# design.net
KiCad netlist of a schematic drawn in EasyEDA Pro
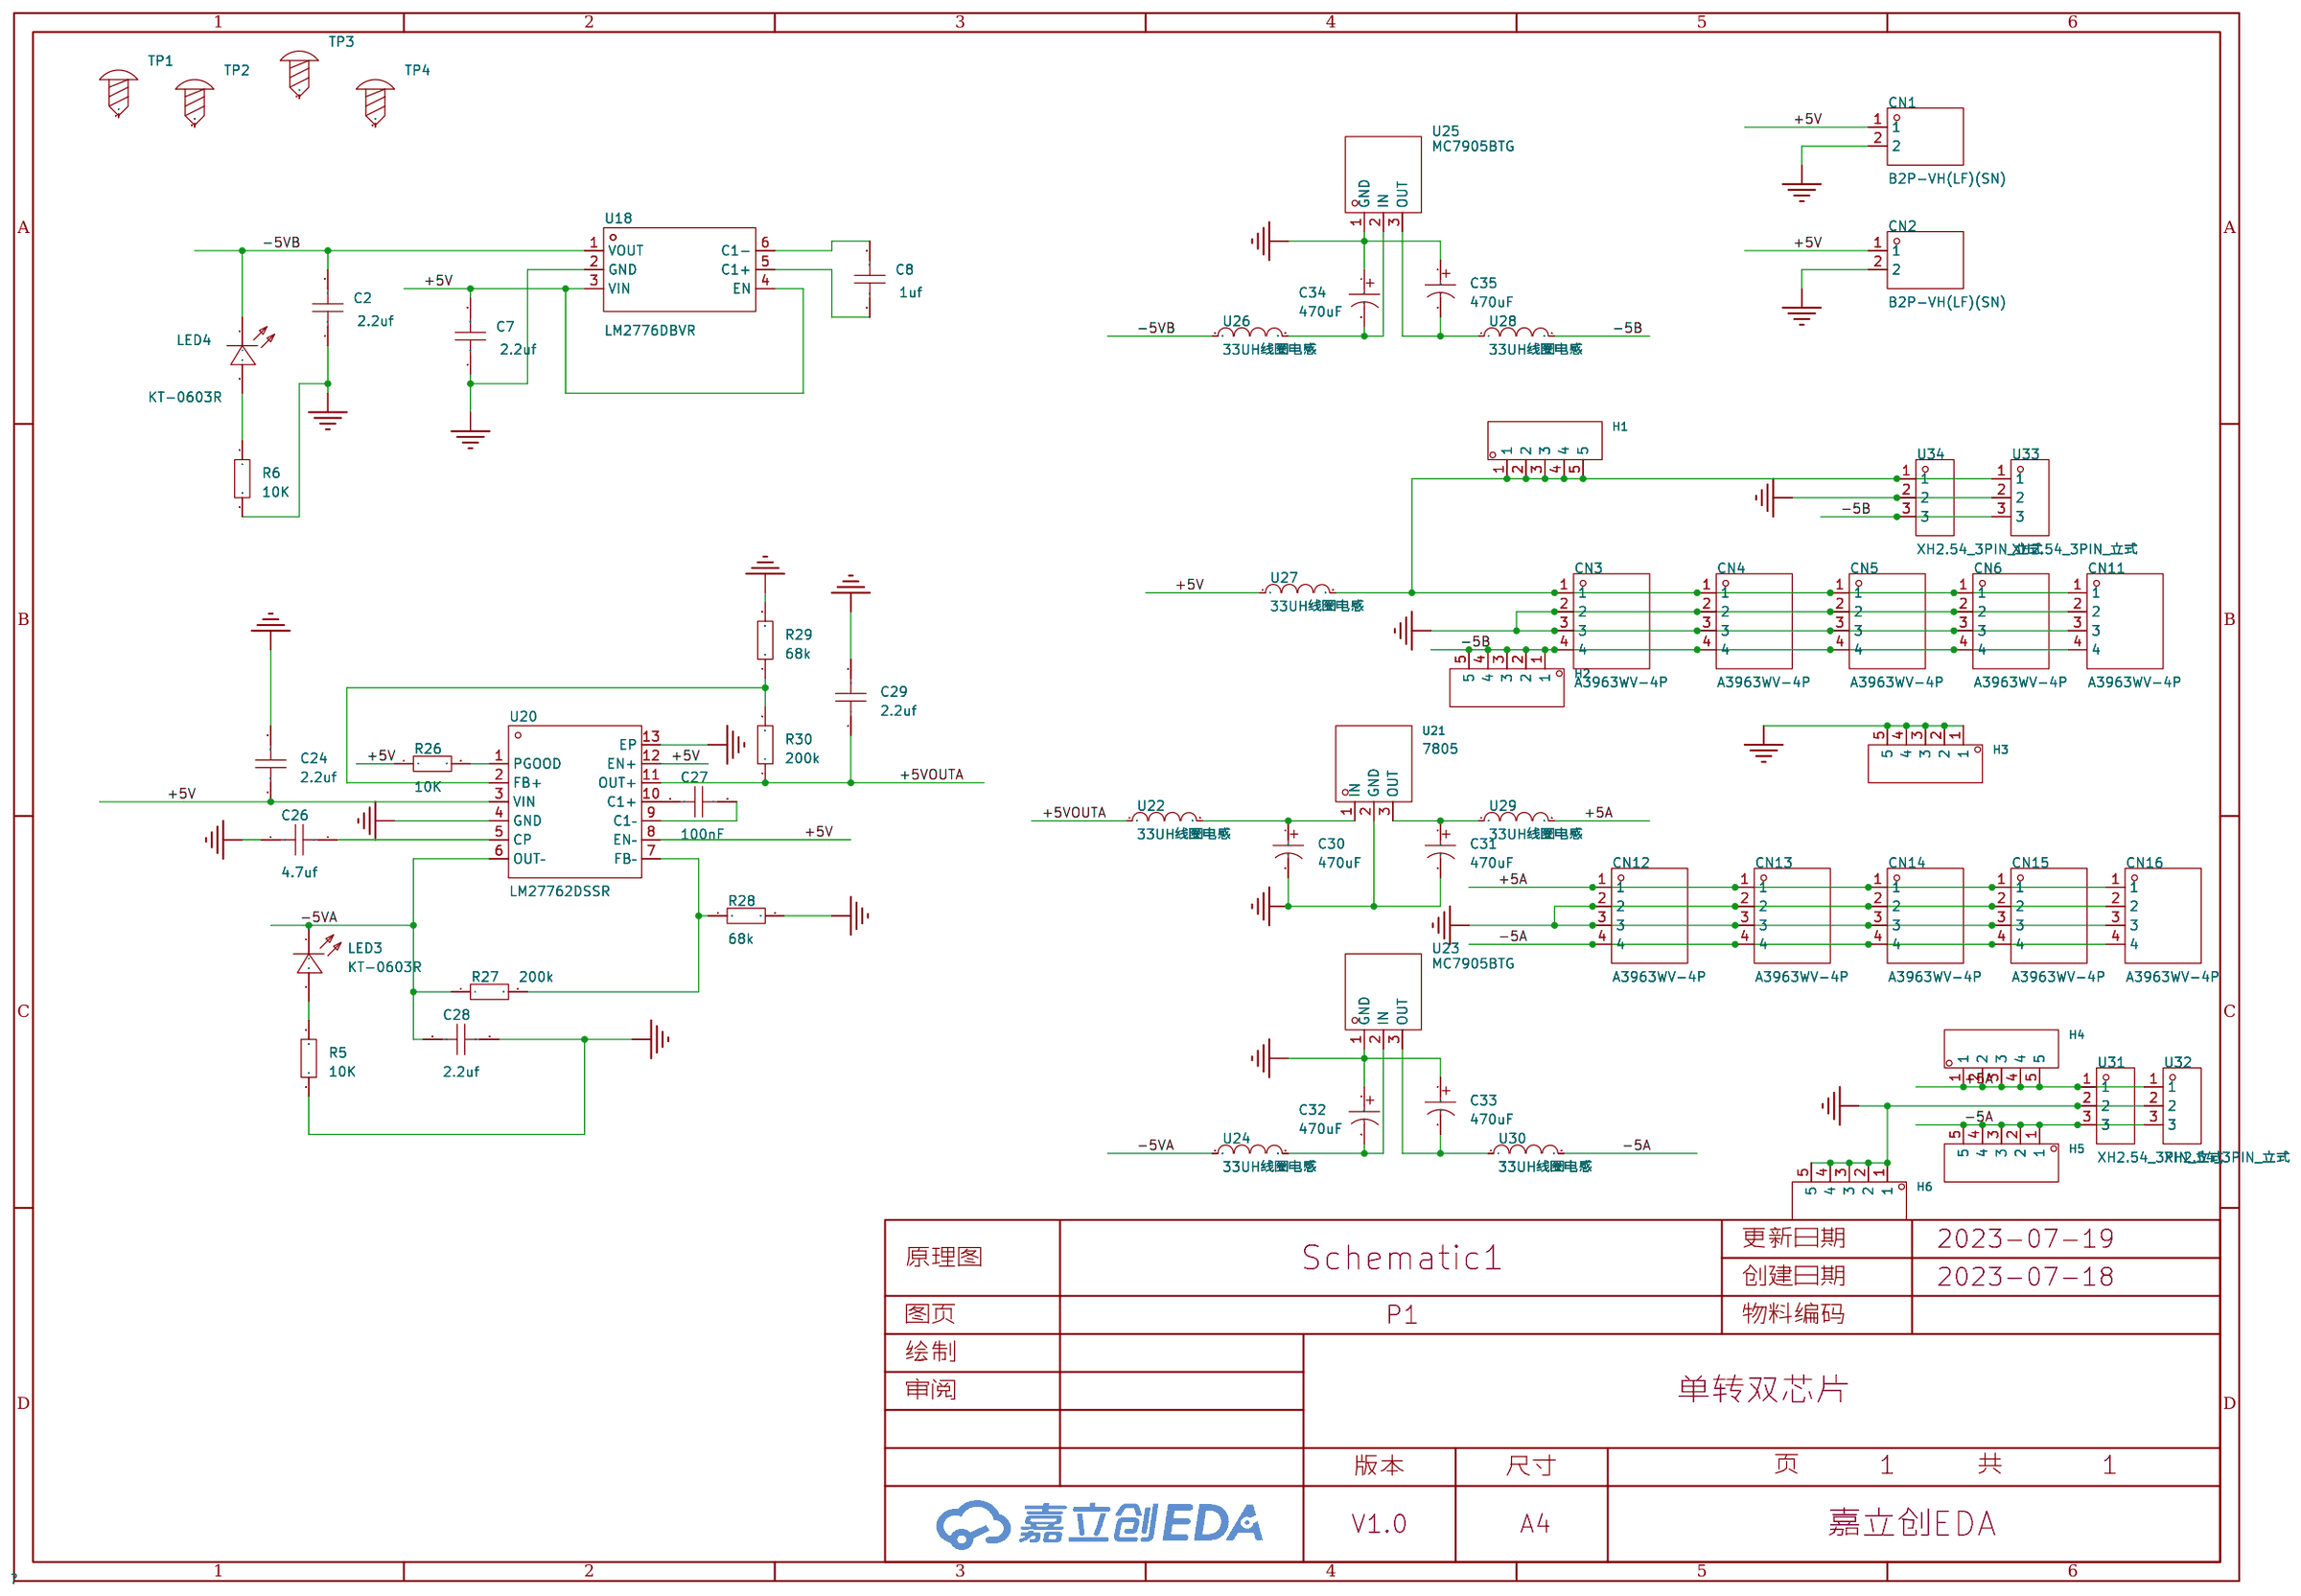
[diagram p0: schematic sheet]

(export (version "E")
  (design (tool "Eeschema 10.0.6"))
  (components
    (comp (ref "C2")
      (value "2.2uf")
      (footprint "easyedapro:C0603")
      (libsource (lib "easyedapro") (part "CapAcitance"))
    )
    (comp (ref "C7")
      (value "2.2uf")
      (footprint "easyedapro:C0603")
      (libsource (lib "easyedapro") (part "CapAcitance"))
    )
    (comp (ref "C8")
      (value "1uf")
      (footprint "easyedapro:C0603")
      (libsource (lib "easyedapro") (part "CapAcitance"))
    )
    (comp (ref "C24")
      (value "2.2uf")
      (footprint "easyedapro:C0603")
      (libsource (lib "easyedapro") (part "CapAcitance"))
    )
    (comp (ref "C26")
      (value "4.7uf")
      (footprint "easyedapro:C0603")
      (libsource (lib "easyedapro") (part "CapAcitance"))
    )
    (comp (ref "C27")
      (value "100nF")
      (footprint "easyedapro:C0603")
      (libsource (lib "easyedapro") (part "CapAcitance"))
    )
    (comp (ref "C28")
      (value "2.2uf")
      (footprint "easyedapro:C0603")
      (libsource (lib "easyedapro") (part "CapAcitance"))
    )
    (comp (ref "C29")
      (value "2.2uf")
      (footprint "easyedapro:C0603")
      (libsource (lib "easyedapro") (part "CapAcitance"))
    )
    (comp (ref "C30")
      (value "470uF")
      (footprint "easyedapro:CAP-TH_BD8.0-P3.50-D0.6-FD")
      (description "容值:470uF;精度:±20%;额定电压:25V;")
      (fields
        (field (name "Manufacturer Part") "KM477M025F12RR0VH2FP0")
        (field (name "Manufacturer") "CX(承兴)")
      )
      (libsource (lib "easyedapro") (part "470uF 25V 8*12"))
    )
    (comp (ref "C31")
      (value "470uF")
      (footprint "easyedapro:CAP-TH_BD8.0-P3.50-D0.6-FD")
      (description "容值:470uF;精度:±20%;额定电压:25V;")
      (fields
        (field (name "Manufacturer Part") "KM477M025F12RR0VH2FP0")
        (field (name "Manufacturer") "CX(承兴)")
      )
      (libsource (lib "easyedapro") (part "470uF 25V 8*12"))
    )
    (comp (ref "C32")
      (value "470uF")
      (footprint "easyedapro:CAP-TH_BD8.0-P3.50-D0.6-FD")
      (description "容值:470uF;精度:±20%;额定电压:25V;")
      (fields
        (field (name "Manufacturer Part") "KM477M025F12RR0VH2FP0")
        (field (name "Manufacturer") "CX(承兴)")
      )
      (libsource (lib "easyedapro") (part "470uF 25V 8*12"))
    )
    (comp (ref "C33")
      (value "470uF")
      (footprint "easyedapro:CAP-TH_BD8.0-P3.50-D0.6-FD")
      (description "容值:470uF;精度:±20%;额定电压:25V;")
      (fields
        (field (name "Manufacturer Part") "KM477M025F12RR0VH2FP0")
        (field (name "Manufacturer") "CX(承兴)")
      )
      (libsource (lib "easyedapro") (part "470uF 25V 8*12"))
    )
    (comp (ref "C34")
      (value "470uF")
      (footprint "easyedapro:CAP-TH_BD8.0-P3.50-D0.6-FD")
      (description "容值:470uF;精度:±20%;额定电压:25V;")
      (fields
        (field (name "Manufacturer Part") "KM477M025F12RR0VH2FP0")
        (field (name "Manufacturer") "CX(承兴)")
      )
      (libsource (lib "easyedapro") (part "470uF 25V 8*12"))
    )
    (comp (ref "C35")
      (value "470uF")
      (footprint "easyedapro:CAP-TH_BD8.0-P3.50-D0.6-FD")
      (description "容值:470uF;精度:±20%;额定电压:25V;")
      (fields
        (field (name "Manufacturer Part") "KM477M025F12RR0VH2FP0")
        (field (name "Manufacturer") "CX(承兴)")
      )
      (libsource (lib "easyedapro") (part "470uF 25V 8*12"))
    )
    (comp (ref "CN1")
      (value "B2P-VH(LF)(SN)")
      (footprint "easyedapro:CONN-TH_B2P-VH-LF-SN")
      (description "参考系列:VH;间距:3.96mm;插针结构:1x2P;排数:1;每排PIN数:2;行距:-;安装方式:-;触头材质:黄铜;")
      (fields (field (name "Manufacturer") "JST"))
      (libsource (lib "easyedapro") (part "B2P-VH(LF)(SN)"))
    )
    (comp (ref "CN2")
      (value "B2P-VH(LF)(SN)")
      (footprint "easyedapro:CONN-TH_B2P-VH-LF-SN")
      (description "参考系列:VH;间距:3.96mm;插针结构:1x2P;排数:1;每排PIN数:2;行距:-;安装方式:-;触头材质:黄铜;")
      (fields (field (name "Manufacturer") "JST"))
      (libsource (lib "easyedapro") (part "B2P-VH(LF)(SN)"))
    )
    (comp (ref "CN3")
      (value "A3963WV-4P")
      (footprint "easyedapro:CONN-TH_A3963WV-4P")
      (description "参考系列:VH;间距:3.96mm;插针结构:1x4P;排数:1;每排PIN数:4;行距:-;安装方式:-;触头材质:黄铜;")
      (fields (field (name "Manufacturer") "CJT(长江连接器)"))
      (libsource (lib "easyedapro") (part "A3963WV-4P"))
    )
    (comp (ref "CN4")
      (value "A3963WV-4P")
      (footprint "easyedapro:CONN-TH_A3963WV-4P")
      (description "参考系列:VH;间距:3.96mm;插针结构:1x4P;排数:1;每排PIN数:4;行距:-;安装方式:-;触头材质:黄铜;")
      (fields (field (name "Manufacturer") "CJT(长江连接器)"))
      (libsource (lib "easyedapro") (part "A3963WV-4P"))
    )
    (comp (ref "CN5")
      (value "A3963WV-4P")
      (footprint "easyedapro:CONN-TH_A3963WV-4P")
      (description "参考系列:VH;间距:3.96mm;插针结构:1x4P;排数:1;每排PIN数:4;行距:-;安装方式:-;触头材质:黄铜;")
      (fields (field (name "Manufacturer") "CJT(长江连接器)"))
      (libsource (lib "easyedapro") (part "A3963WV-4P"))
    )
    (comp (ref "CN6")
      (value "A3963WV-4P")
      (footprint "easyedapro:CONN-TH_A3963WV-4P")
      (description "参考系列:VH;间距:3.96mm;插针结构:1x4P;排数:1;每排PIN数:4;行距:-;安装方式:-;触头材质:黄铜;")
      (fields (field (name "Manufacturer") "CJT(长江连接器)"))
      (libsource (lib "easyedapro") (part "A3963WV-4P"))
    )
    (comp (ref "CN11")
      (value "A3963WV-4P")
      (footprint "easyedapro:CONN-TH_A3963WV-4P")
      (description "参考系列:VH;间距:3.96mm;插针结构:1x4P;排数:1;每排PIN数:4;行距:-;安装方式:-;触头材质:黄铜;")
      (fields (field (name "Manufacturer") "CJT(长江连接器)"))
      (libsource (lib "easyedapro") (part "A3963WV-4P"))
    )
    (comp (ref "CN12")
      (value "A3963WV-4P")
      (footprint "easyedapro:CONN-TH_A3963WV-4P")
      (description "参考系列:VH;间距:3.96mm;插针结构:1x4P;排数:1;每排PIN数:4;行距:-;安装方式:-;触头材质:黄铜;")
      (fields (field (name "Manufacturer") "CJT(长江连接器)"))
      (libsource (lib "easyedapro") (part "A3963WV-4P"))
    )
    (comp (ref "CN13")
      (value "A3963WV-4P")
      (footprint "easyedapro:CONN-TH_A3963WV-4P")
      (description "参考系列:VH;间距:3.96mm;插针结构:1x4P;排数:1;每排PIN数:4;行距:-;安装方式:-;触头材质:黄铜;")
      (fields (field (name "Manufacturer") "CJT(长江连接器)"))
      (libsource (lib "easyedapro") (part "A3963WV-4P"))
    )
    (comp (ref "CN14")
      (value "A3963WV-4P")
      (footprint "easyedapro:CONN-TH_A3963WV-4P")
      (description "参考系列:VH;间距:3.96mm;插针结构:1x4P;排数:1;每排PIN数:4;行距:-;安装方式:-;触头材质:黄铜;")
      (fields (field (name "Manufacturer") "CJT(长江连接器)"))
      (libsource (lib "easyedapro") (part "A3963WV-4P"))
    )
    (comp (ref "CN15")
      (value "A3963WV-4P")
      (footprint "easyedapro:CONN-TH_A3963WV-4P")
      (description "参考系列:VH;间距:3.96mm;插针结构:1x4P;排数:1;每排PIN数:4;行距:-;安装方式:-;触头材质:黄铜;")
      (fields (field (name "Manufacturer") "CJT(长江连接器)"))
      (libsource (lib "easyedapro") (part "A3963WV-4P"))
    )
    (comp (ref "CN16")
      (value "A3963WV-4P")
      (footprint "easyedapro:CONN-TH_A3963WV-4P")
      (description "参考系列:VH;间距:3.96mm;插针结构:1x4P;排数:1;每排PIN数:4;行距:-;安装方式:-;触头材质:黄铜;")
      (fields (field (name "Manufacturer") "CJT(长江连接器)"))
      (libsource (lib "easyedapro") (part "A3963WV-4P"))
    )
    (comp (ref "H1")
      (value "~")
      (footprint "easyedapro:HDR-TH_5P-P2.54-V-M")
      (libsource (lib "easyedapro") (part "MTP125-1105S1"))
    )
    (comp (ref "H2")
      (value "~")
      (footprint "easyedapro:HDR-TH_5P-P2.54-V-M")
      (libsource (lib "easyedapro") (part "MTP125-1105S1"))
    )
    (comp (ref "H3")
      (value "~")
      (footprint "easyedapro:HDR-TH_5P-P2.54-V-M")
      (libsource (lib "easyedapro") (part "MTP125-1105S1"))
    )
    (comp (ref "H4")
      (value "~")
      (footprint "easyedapro:HDR-TH_5P-P2.54-V-M")
      (libsource (lib "easyedapro") (part "MTP125-1105S1"))
    )
    (comp (ref "H5")
      (value "~")
      (footprint "easyedapro:HDR-TH_5P-P2.54-V-M")
      (libsource (lib "easyedapro") (part "MTP125-1105S1"))
    )
    (comp (ref "H6")
      (value "~")
      (footprint "easyedapro:HDR-TH_5P-P2.54-V-M")
      (libsource (lib "easyedapro") (part "MTP125-1105S1"))
    )
    (comp (ref "LED3")
      (value "KT-0603R")
      (footprint "easyedapro:LED0603-RD")
      (description "发光颜色:红灯;二极管配置:-;透镜颜色:-;主波长:-;色温:-;功率:-;发光角度:-;安装方式:-;工作温度:-40℃~+85℃;")
      (fields (field (name "Manufacturer") "KENTO"))
      (libsource (lib "easyedapro") (part "KT-0603R"))
    )
    (comp (ref "LED4")
      (value "KT-0603R")
      (footprint "easyedapro:LED0603-RD")
      (description "发光颜色:红灯;二极管配置:-;透镜颜色:-;主波长:-;色温:-;功率:-;发光角度:-;安装方式:-;工作温度:-40℃~+85℃;")
      (fields (field (name "Manufacturer") "KENTO"))
      (libsource (lib "easyedapro") (part "KT-0603R"))
    )
    (comp (ref "R5") (value "10K") (footprint "easyedapro:R0603") (libsource (lib "easyedapro") (part "电阻")))
    (comp (ref "R6") (value "10K") (footprint "easyedapro:R0603") (libsource (lib "easyedapro") (part "电阻")))
    (comp (ref "R26") (value "10K") (footprint "easyedapro:R0603") (libsource (lib "easyedapro") (part "电阻")))
    (comp (ref "R27")
      (value "200k")
      (footprint "easyedapro:R0603")
      (libsource (lib "easyedapro") (part "电阻"))
    )
    (comp (ref "R28") (value "68k") (footprint "easyedapro:R0603") (libsource (lib "easyedapro") (part "电阻")))
    (comp (ref "R29") (value "68k") (footprint "easyedapro:R0603") (libsource (lib "easyedapro") (part "电阻")))
    (comp (ref "R30")
      (value "200k")
      (footprint "easyedapro:R0603")
      (libsource (lib "easyedapro") (part "电阻"))
    )
    (comp (ref "TP1") (value "~") (footprint "easyedapro:M3螺丝") (libsource (lib "easyedapro") (part "螺丝孔")))
    (comp (ref "TP2") (value "~") (footprint "easyedapro:M3螺丝") (libsource (lib "easyedapro") (part "螺丝孔")))
    (comp (ref "TP3") (value "~") (footprint "easyedapro:M3螺丝") (libsource (lib "easyedapro") (part "螺丝孔")))
    (comp (ref "TP4") (value "~") (footprint "easyedapro:M3螺丝") (libsource (lib "easyedapro") (part "螺丝孔")))
    (comp (ref "U18")
      (value "LM2776DBVR")
      (footprint "easyedapro:SOT-23-6_L2.9-W1.6-P0.95-LS2.8-BR")
      (description "可输出电流:200mA;开关工作频率:2MHz;输出类型:Fixed;输出电压的路数:1;功能类型:Ratiometric;输出配置:Negative;")
      (fields (field (name "Manufacturer") "TI(德州仪器)"))
      (libsource (lib "easyedapro") (part "LM2776DBVR"))
    )
    (comp (ref "U20")
      (value "LM27762DSSR")
      (footprint "easyedapro:WSON-12_L3.0-W2.0-P0.50-BL-EP")
      (description "功能类型:电荷泵;同步整流:否;输出通道数:2;拓扑结构:-;输入电压:2.7V~5.5V;输出电压:-5V~-1.5V；1.5V~5V;输出电流(最大值):250mA;开关频率:2.3MHz;")
      (fields (field (name "Manufacturer") "TI(德州仪器)"))
      (libsource (lib "easyedapro") (part "LM27762DSSR"))
    )
    (comp (ref "U21")
      (value "7805")
      (footprint "easyedapro:TO-220-3_L10.2-W4.5-P2.54-L-1")
      (description "输出类型:固定;输出极性:正;最大输入电压:35V;输出电压:5V;输出电流:1.5A;电源纹波抑制比(PSRR):62dB@(120Hz);")
      (fields (field (name "Manufacturer") "SY(顺烨）"))
      (libsource (lib "easyedapro") (part "7805_C4944936"))
    )
    (comp (ref "U22")
      (value "33UH线圈电感")
      (footprint "easyedapro:IND-TH_L5.4-W5.0")
      (libsource (lib "easyedapro") (part "33UH线圈电感"))
    )
    (comp (ref "U23")
      (value "MC7905BTG")
      (footprint "easyedapro:TO-220-3_L10.0-W4.5-P2.54-T")
      (description "输出类型:固定;输出极性:负;最大输入电压:35V;输出电压:5V;输出电流:1A;电源纹波抑制比(PSRR):70dB@(120Hz);")
      (fields (field (name "Manufacturer") "onsemi(安森美)"))
      (libsource (lib "easyedapro") (part "MC7905BTG"))
    )
    (comp (ref "U24")
      (value "33UH线圈电感")
      (footprint "easyedapro:IND-TH_L5.4-W5.0")
      (libsource (lib "easyedapro") (part "33UH线圈电感"))
    )
    (comp (ref "U25")
      (value "MC7905BTG")
      (footprint "easyedapro:TO-220-3_L10.0-W4.5-P2.54-T")
      (description "输出类型:固定;输出极性:负;最大输入电压:35V;输出电压:5V;输出电流:1A;电源纹波抑制比(PSRR):70dB@(120Hz);")
      (fields (field (name "Manufacturer") "onsemi(安森美)"))
      (libsource (lib "easyedapro") (part "MC7905BTG"))
    )
    (comp (ref "U26")
      (value "33UH线圈电感")
      (footprint "easyedapro:IND-TH_L5.4-W5.0")
      (libsource (lib "easyedapro") (part "33UH线圈电感"))
    )
    (comp (ref "U27")
      (value "33UH线圈电感")
      (footprint "easyedapro:IND-TH_L5.4-W5.0")
      (libsource (lib "easyedapro") (part "33UH线圈电感"))
    )
    (comp (ref "U28")
      (value "33UH线圈电感")
      (footprint "easyedapro:IND-TH_L5.4-W5.0")
      (libsource (lib "easyedapro") (part "33UH线圈电感"))
    )
    (comp (ref "U29")
      (value "33UH线圈电感")
      (footprint "easyedapro:IND-TH_L5.4-W5.0")
      (libsource (lib "easyedapro") (part "33UH线圈电感"))
    )
    (comp (ref "U30")
      (value "33UH线圈电感")
      (footprint "easyedapro:IND-TH_L5.4-W5.0")
      (libsource (lib "easyedapro") (part "33UH线圈电感"))
    )
    (comp (ref "U31")
      (value "XH2.54_3PIN_立式")
      (footprint "easyedapro:CONN-TH_XH2.54_3PIN")
      (libsource (lib "easyedapro") (part "XH2.54_3PIN"))
    )
    (comp (ref "U32")
      (value "XH2.54_3PIN_立式")
      (footprint "easyedapro:CONN-TH_XH2.54_3PIN")
      (libsource (lib "easyedapro") (part "XH2.54_3PIN"))
    )
    (comp (ref "U33")
      (value "XH2.54_3PIN_立式")
      (footprint "easyedapro:CONN-TH_XH2.54_3PIN")
      (libsource (lib "easyedapro") (part "XH2.54_3PIN"))
    )
    (comp (ref "U34")
      (value "XH2.54_3PIN_立式")
      (footprint "easyedapro:CONN-TH_XH2.54_3PIN")
      (libsource (lib "easyedapro") (part "XH2.54_3PIN"))
    )
  )
  (nets
    (net (code "1") (name "/+5A") (class "Default")
      (node (ref "CN12") (pin "1") (pinfunction "1_1") (pintype "input"))
      (node (ref "CN13") (pin "1") (pinfunction "1_1") (pintype "input"))
      (node (ref "CN14") (pin "1") (pinfunction "1_1") (pintype "input"))
      (node (ref "CN15") (pin "1") (pinfunction "1_1") (pintype "input"))
      (node (ref "CN16") (pin "1") (pinfunction "1_1") (pintype "input"))
      (node (ref "H4") (pin "1") (pinfunction "1_1") (pintype "input"))
      (node (ref "H4") (pin "2") (pinfunction "2_2") (pintype "input"))
      (node (ref "H4") (pin "3") (pinfunction "3_3") (pintype "input"))
      (node (ref "H4") (pin "4") (pinfunction "4_4") (pintype "input"))
      (node (ref "H4") (pin "5") (pinfunction "5_5") (pintype "input"))
      (node (ref "U29") (pin "2") (pinfunction "2_2") (pintype "input"))
      (node (ref "U31") (pin "1") (pinfunction "1_1") (pintype "input"))
      (node (ref "U32") (pin "1") (pinfunction "1_1") (pintype "input"))
    )
    (net (code "2") (name "/+5V") (class "Default")
      (node (ref "C24") (pin "1") (pinfunction "1_1") (pintype "input"))
      (node (ref "C7") (pin "2") (pinfunction "2_2") (pintype "input"))
      (node (ref "CN1") (pin "1") (pinfunction "1_1") (pintype "input"))
      (node (ref "CN2") (pin "1") (pinfunction "1_1") (pintype "input"))
      (node (ref "R26") (pin "1") (pinfunction "1_1") (pintype "input"))
      (node (ref "U18") (pin "3") (pinfunction "VIN_3") (pintype "input"))
      (node (ref "U18") (pin "4") (pinfunction "EN_4") (pintype "input"))
      (node (ref "U20") (pin "12") (pinfunction "EN+_12") (pintype "input"))
      (node (ref "U20") (pin "3") (pinfunction "VIN_3") (pintype "input"))
      (node (ref "U20") (pin "8") (pinfunction "EN–_8") (pintype "input"))
      (node (ref "U27") (pin "1") (pinfunction "1_1") (pintype "input"))
    )
    (net (code "3") (name "/+5VOUTA") (class "Default")
      (node (ref "C29") (pin "1") (pinfunction "1_1") (pintype "input"))
      (node (ref "R30") (pin "1") (pinfunction "1_1") (pintype "input"))
      (node (ref "U20") (pin "11") (pinfunction "OUT+_11") (pintype "input"))
      (node (ref "U22") (pin "1") (pinfunction "1_1") (pintype "input"))
    )
    (net (code "4") (name "/-5A") (class "Default")
      (node (ref "CN12") (pin "4") (pinfunction "4_4") (pintype "input"))
      (node (ref "CN13") (pin "4") (pinfunction "4_4") (pintype "input"))
      (node (ref "CN14") (pin "4") (pinfunction "4_4") (pintype "input"))
      (node (ref "CN15") (pin "4") (pinfunction "4_4") (pintype "input"))
      (node (ref "CN16") (pin "4") (pinfunction "4_4") (pintype "input"))
      (node (ref "H5") (pin "1") (pinfunction "1_1") (pintype "input"))
      (node (ref "H5") (pin "2") (pinfunction "2_2") (pintype "input"))
      (node (ref "H5") (pin "3") (pinfunction "3_3") (pintype "input"))
      (node (ref "H5") (pin "4") (pinfunction "4_4") (pintype "input"))
      (node (ref "H5") (pin "5") (pinfunction "5_5") (pintype "input"))
      (node (ref "U30") (pin "2") (pinfunction "2_2") (pintype "input"))
      (node (ref "U31") (pin "3") (pinfunction "3_3") (pintype "input"))
      (node (ref "U32") (pin "3") (pinfunction "3_3") (pintype "input"))
    )
    (net (code "5") (name "/-5B") (class "Default")
      (node (ref "CN11") (pin "4") (pinfunction "4_4") (pintype "input"))
      (node (ref "CN3") (pin "4") (pinfunction "4_4") (pintype "input"))
      (node (ref "CN4") (pin "4") (pinfunction "4_4") (pintype "input"))
      (node (ref "CN5") (pin "4") (pinfunction "4_4") (pintype "input"))
      (node (ref "CN6") (pin "4") (pinfunction "4_4") (pintype "input"))
      (node (ref "H2") (pin "1") (pinfunction "1_1") (pintype "input"))
      (node (ref "H2") (pin "2") (pinfunction "2_2") (pintype "input"))
      (node (ref "H2") (pin "3") (pinfunction "3_3") (pintype "input"))
      (node (ref "H2") (pin "4") (pinfunction "4_4") (pintype "input"))
      (node (ref "H2") (pin "5") (pinfunction "5_5") (pintype "input"))
      (node (ref "U28") (pin "2") (pinfunction "2_2") (pintype "input"))
      (node (ref "U33") (pin "3") (pinfunction "3_3") (pintype "input"))
      (node (ref "U34") (pin "3") (pinfunction "3_3") (pintype "input"))
    )
    (net (code "6") (name "/-5VA") (class "Default")
      (node (ref "C28") (pin "2") (pinfunction "2_2") (pintype "input"))
      (node (ref "LED3") (pin "1") (pinfunction "K_1") (pintype "input"))
      (node (ref "R27") (pin "1") (pinfunction "1_1") (pintype "input"))
      (node (ref "U20") (pin "6") (pinfunction "OUT–_6") (pintype "input"))
      (node (ref "U24") (pin "1") (pinfunction "1_1") (pintype "input"))
    )
    (net (code "7") (name "/-5VB") (class "Default")
      (node (ref "C2") (pin "2") (pinfunction "2_2") (pintype "input"))
      (node (ref "LED4") (pin "1") (pinfunction "K_1") (pintype "input"))
      (node (ref "U18") (pin "1") (pinfunction "VOUT_1") (pintype "input"))
      (node (ref "U26") (pin "1") (pinfunction "1_1") (pintype "input"))
    )
    (net (code "8") (name "GND") (class "Default")
      (node (ref "C2") (pin "1") (pinfunction "1_1") (pintype "input"))
      (node (ref "C24") (pin "2") (pinfunction "2_2") (pintype "input"))
      (node (ref "C26") (pin "2") (pinfunction "2_2") (pintype "input"))
      (node (ref "C28") (pin "1") (pinfunction "1_1") (pintype "input"))
      (node (ref "C29") (pin "2") (pinfunction "2_2") (pintype "input"))
      (node (ref "C30") (pin "2") (pinfunction "2_2") (pintype "input"))
      (node (ref "C31") (pin "2") (pinfunction "2_2") (pintype "input"))
      (node (ref "C32") (pin "1") (pinfunction "1_1") (pintype "input"))
      (node (ref "C33") (pin "1") (pinfunction "1_1") (pintype "input"))
      (node (ref "C34") (pin "1") (pinfunction "1_1") (pintype "input"))
      (node (ref "C35") (pin "1") (pinfunction "1_1") (pintype "input"))
      (node (ref "C7") (pin "1") (pinfunction "1_1") (pintype "input"))
      (node (ref "CN1") (pin "2") (pinfunction "2_2") (pintype "input"))
      (node (ref "CN11") (pin "2") (pinfunction "2_2") (pintype "input"))
      (node (ref "CN11") (pin "3") (pinfunction "3_3") (pintype "input"))
      (node (ref "CN12") (pin "2") (pinfunction "2_2") (pintype "input"))
      (node (ref "CN12") (pin "3") (pinfunction "3_3") (pintype "input"))
      (node (ref "CN13") (pin "2") (pinfunction "2_2") (pintype "input"))
      (node (ref "CN13") (pin "3") (pinfunction "3_3") (pintype "input"))
      (node (ref "CN14") (pin "2") (pinfunction "2_2") (pintype "input"))
      (node (ref "CN14") (pin "3") (pinfunction "3_3") (pintype "input"))
      (node (ref "CN15") (pin "2") (pinfunction "2_2") (pintype "input"))
      (node (ref "CN15") (pin "3") (pinfunction "3_3") (pintype "input"))
      (node (ref "CN16") (pin "2") (pinfunction "2_2") (pintype "input"))
      (node (ref "CN16") (pin "3") (pinfunction "3_3") (pintype "input"))
      (node (ref "CN2") (pin "2") (pinfunction "2_2") (pintype "input"))
      (node (ref "CN3") (pin "2") (pinfunction "2_2") (pintype "input"))
      (node (ref "CN3") (pin "3") (pinfunction "3_3") (pintype "input"))
      (node (ref "CN4") (pin "2") (pinfunction "2_2") (pintype "input"))
      (node (ref "CN4") (pin "3") (pinfunction "3_3") (pintype "input"))
      (node (ref "CN5") (pin "2") (pinfunction "2_2") (pintype "input"))
      (node (ref "CN5") (pin "3") (pinfunction "3_3") (pintype "input"))
      (node (ref "CN6") (pin "2") (pinfunction "2_2") (pintype "input"))
      (node (ref "CN6") (pin "3") (pinfunction "3_3") (pintype "input"))
      (node (ref "H3") (pin "1") (pinfunction "1_1") (pintype "input"))
      (node (ref "H3") (pin "2") (pinfunction "2_2") (pintype "input"))
      (node (ref "H3") (pin "3") (pinfunction "3_3") (pintype "input"))
      (node (ref "H3") (pin "4") (pinfunction "4_4") (pintype "input"))
      (node (ref "H3") (pin "5") (pinfunction "5_5") (pintype "input"))
      (node (ref "H6") (pin "1") (pinfunction "1_1") (pintype "input"))
      (node (ref "H6") (pin "2") (pinfunction "2_2") (pintype "input"))
      (node (ref "H6") (pin "3") (pinfunction "3_3") (pintype "input"))
      (node (ref "H6") (pin "4") (pinfunction "4_4") (pintype "input"))
      (node (ref "H6") (pin "5") (pinfunction "5_5") (pintype "input"))
      (node (ref "R28") (pin "2") (pinfunction "2_2") (pintype "input"))
      (node (ref "R29") (pin "2") (pinfunction "2_2") (pintype "input"))
      (node (ref "R5") (pin "2") (pinfunction "2_2") (pintype "input"))
      (node (ref "R6") (pin "2") (pinfunction "2_2") (pintype "input"))
      (node (ref "U18") (pin "2") (pinfunction "GND_2") (pintype "input"))
      (node (ref "U20") (pin "13") (pinfunction "EP_13") (pintype "input"))
      (node (ref "U20") (pin "4") (pinfunction "GND_4") (pintype "input"))
      (node (ref "U21") (pin "2") (pinfunction "GND_2") (pintype "input"))
      (node (ref "U23") (pin "1") (pinfunction "GND_1") (pintype "input"))
      (node (ref "U25") (pin "1") (pinfunction "GND_1") (pintype "input"))
      (node (ref "U31") (pin "2") (pinfunction "2_2") (pintype "input"))
      (node (ref "U32") (pin "2") (pinfunction "2_2") (pintype "input"))
      (node (ref "U33") (pin "2") (pinfunction "2_2") (pintype "input"))
      (node (ref "U34") (pin "2") (pinfunction "2_2") (pintype "input"))
    )
    (net (code "9") (name "Net-(CN11-Pad1)") (class "Default")
      (node (ref "CN11") (pin "1") (pinfunction "1_1") (pintype "input"))
      (node (ref "CN3") (pin "1") (pinfunction "1_1") (pintype "input"))
      (node (ref "CN4") (pin "1") (pinfunction "1_1") (pintype "input"))
      (node (ref "CN5") (pin "1") (pinfunction "1_1") (pintype "input"))
      (node (ref "CN6") (pin "1") (pinfunction "1_1") (pintype "input"))
      (node (ref "H1") (pin "1") (pinfunction "1_1") (pintype "input"))
      (node (ref "H1") (pin "2") (pinfunction "2_2") (pintype "input"))
      (node (ref "H1") (pin "3") (pinfunction "3_3") (pintype "input"))
      (node (ref "H1") (pin "4") (pinfunction "4_4") (pintype "input"))
      (node (ref "H1") (pin "5") (pinfunction "5_5") (pintype "input"))
      (node (ref "U27") (pin "2") (pinfunction "2_2") (pintype "input"))
      (node (ref "U33") (pin "1") (pinfunction "1_1") (pintype "input"))
      (node (ref "U34") (pin "1") (pinfunction "1_1") (pintype "input"))
    )
    (net (code "10") (name "Net-(LED3-A)") (class "Default")
      (node (ref "LED3") (pin "2") (pinfunction "A_2") (pintype "input"))
      (node (ref "R5") (pin "1") (pinfunction "1_1") (pintype "input"))
    )
    (net (code "11") (name "Net-(LED4-A)") (class "Default")
      (node (ref "LED4") (pin "2") (pinfunction "A_2") (pintype "input"))
      (node (ref "R6") (pin "1") (pinfunction "1_1") (pintype "input"))
    )
    (net (code "12") (name "Net-(U18-C1+)") (class "Default")
      (node (ref "C8") (pin "1") (pinfunction "1_1") (pintype "input"))
      (node (ref "U18") (pin "5") (pinfunction "C1+_5") (pintype "input"))
    )
    (net (code "13") (name "Net-(U18-C1-)") (class "Default")
      (node (ref "C8") (pin "2") (pinfunction "2_2") (pintype "input"))
      (node (ref "U18") (pin "6") (pinfunction "C1-_6") (pintype "input"))
    )
    (net (code "14") (name "Net-(U20-C1+)") (class "Default")
      (node (ref "C27") (pin "1") (pinfunction "1_1") (pintype "input"))
      (node (ref "U20") (pin "10") (pinfunction "C1+_10") (pintype "input"))
    )
    (net (code "15") (name "Net-(U20-C1–)") (class "Default")
      (node (ref "C27") (pin "2") (pinfunction "2_2") (pintype "input"))
      (node (ref "U20") (pin "9") (pinfunction "C1–_9") (pintype "input"))
    )
    (net (code "16") (name "Net-(U20-CP)") (class "Default")
      (node (ref "C26") (pin "1") (pinfunction "1_1") (pintype "input"))
      (node (ref "U20") (pin "5") (pinfunction "CP_5") (pintype "input"))
    )
    (net (code "17") (name "Net-(U20-FB+)") (class "Default")
      (node (ref "R29") (pin "1") (pinfunction "1_1") (pintype "input"))
      (node (ref "R30") (pin "2") (pinfunction "2_2") (pintype "input"))
      (node (ref "U20") (pin "2") (pinfunction "FB+_2") (pintype "input"))
    )
    (net (code "18") (name "Net-(U20-FB–)") (class "Default")
      (node (ref "R27") (pin "2") (pinfunction "2_2") (pintype "input"))
      (node (ref "R28") (pin "1") (pinfunction "1_1") (pintype "input"))
      (node (ref "U20") (pin "7") (pinfunction "FB–_7") (pintype "input"))
    )
    (net (code "19") (name "Net-(U20-PGOOD)") (class "Default")
      (node (ref "R26") (pin "2") (pinfunction "2_2") (pintype "input"))
      (node (ref "U20") (pin "1") (pinfunction "PGOOD_1") (pintype "input"))
    )
    (net (code "20") (name "Net-(U21-IN)") (class "Default")
      (node (ref "C30") (pin "1") (pinfunction "1_1") (pintype "input"))
      (node (ref "U21") (pin "1") (pinfunction "IN_1") (pintype "input"))
      (node (ref "U22") (pin "2") (pinfunction "2_2") (pintype "input"))
    )
    (net (code "21") (name "Net-(U21-OUT)") (class "Default")
      (node (ref "C31") (pin "1") (pinfunction "1_1") (pintype "input"))
      (node (ref "U21") (pin "3") (pinfunction "OUT_3") (pintype "input"))
      (node (ref "U29") (pin "1") (pinfunction "1_1") (pintype "input"))
    )
    (net (code "22") (name "Net-(U23-IN)") (class "Default")
      (node (ref "C32") (pin "2") (pinfunction "2_2") (pintype "input"))
      (node (ref "U23") (pin "2") (pinfunction "IN_2") (pintype "input"))
      (node (ref "U24") (pin "2") (pinfunction "2_2") (pintype "input"))
    )
    (net (code "23") (name "Net-(U23-OUT)") (class "Default")
      (node (ref "C33") (pin "2") (pinfunction "2_2") (pintype "input"))
      (node (ref "U23") (pin "3") (pinfunction "OUT_3") (pintype "input"))
      (node (ref "U30") (pin "1") (pinfunction "1_1") (pintype "input"))
    )
    (net (code "24") (name "Net-(U25-IN)") (class "Default")
      (node (ref "C34") (pin "2") (pinfunction "2_2") (pintype "input"))
      (node (ref "U25") (pin "2") (pinfunction "IN_2") (pintype "input"))
      (node (ref "U26") (pin "2") (pinfunction "2_2") (pintype "input"))
    )
    (net (code "25") (name "Net-(U25-OUT)") (class "Default")
      (node (ref "C35") (pin "2") (pinfunction "2_2") (pintype "input"))
      (node (ref "U25") (pin "3") (pinfunction "OUT_3") (pintype "input"))
      (node (ref "U28") (pin "1") (pinfunction "1_1") (pintype "input"))
    )
    (net (code "26") (name "unconnected-(TP1-Pad1)") (class "Default")
      (node (ref "TP1") (pin "1") (pinfunction "1_1") (pintype "input"))
    )
    (net (code "27") (name "unconnected-(TP2-Pad1)") (class "Default")
      (node (ref "TP2") (pin "1") (pinfunction "1_1") (pintype "input"))
    )
    (net (code "28") (name "unconnected-(TP3-Pad1)") (class "Default")
      (node (ref "TP3") (pin "1") (pinfunction "1_1") (pintype "input"))
    )
    (net (code "29") (name "unconnected-(TP4-Pad1)") (class "Default")
      (node (ref "TP4") (pin "1") (pinfunction "1_1") (pintype "input"))
    )
  )
)
